# 10_Clock.net
KiCad netlist of a schematic drawn in Altium Designer
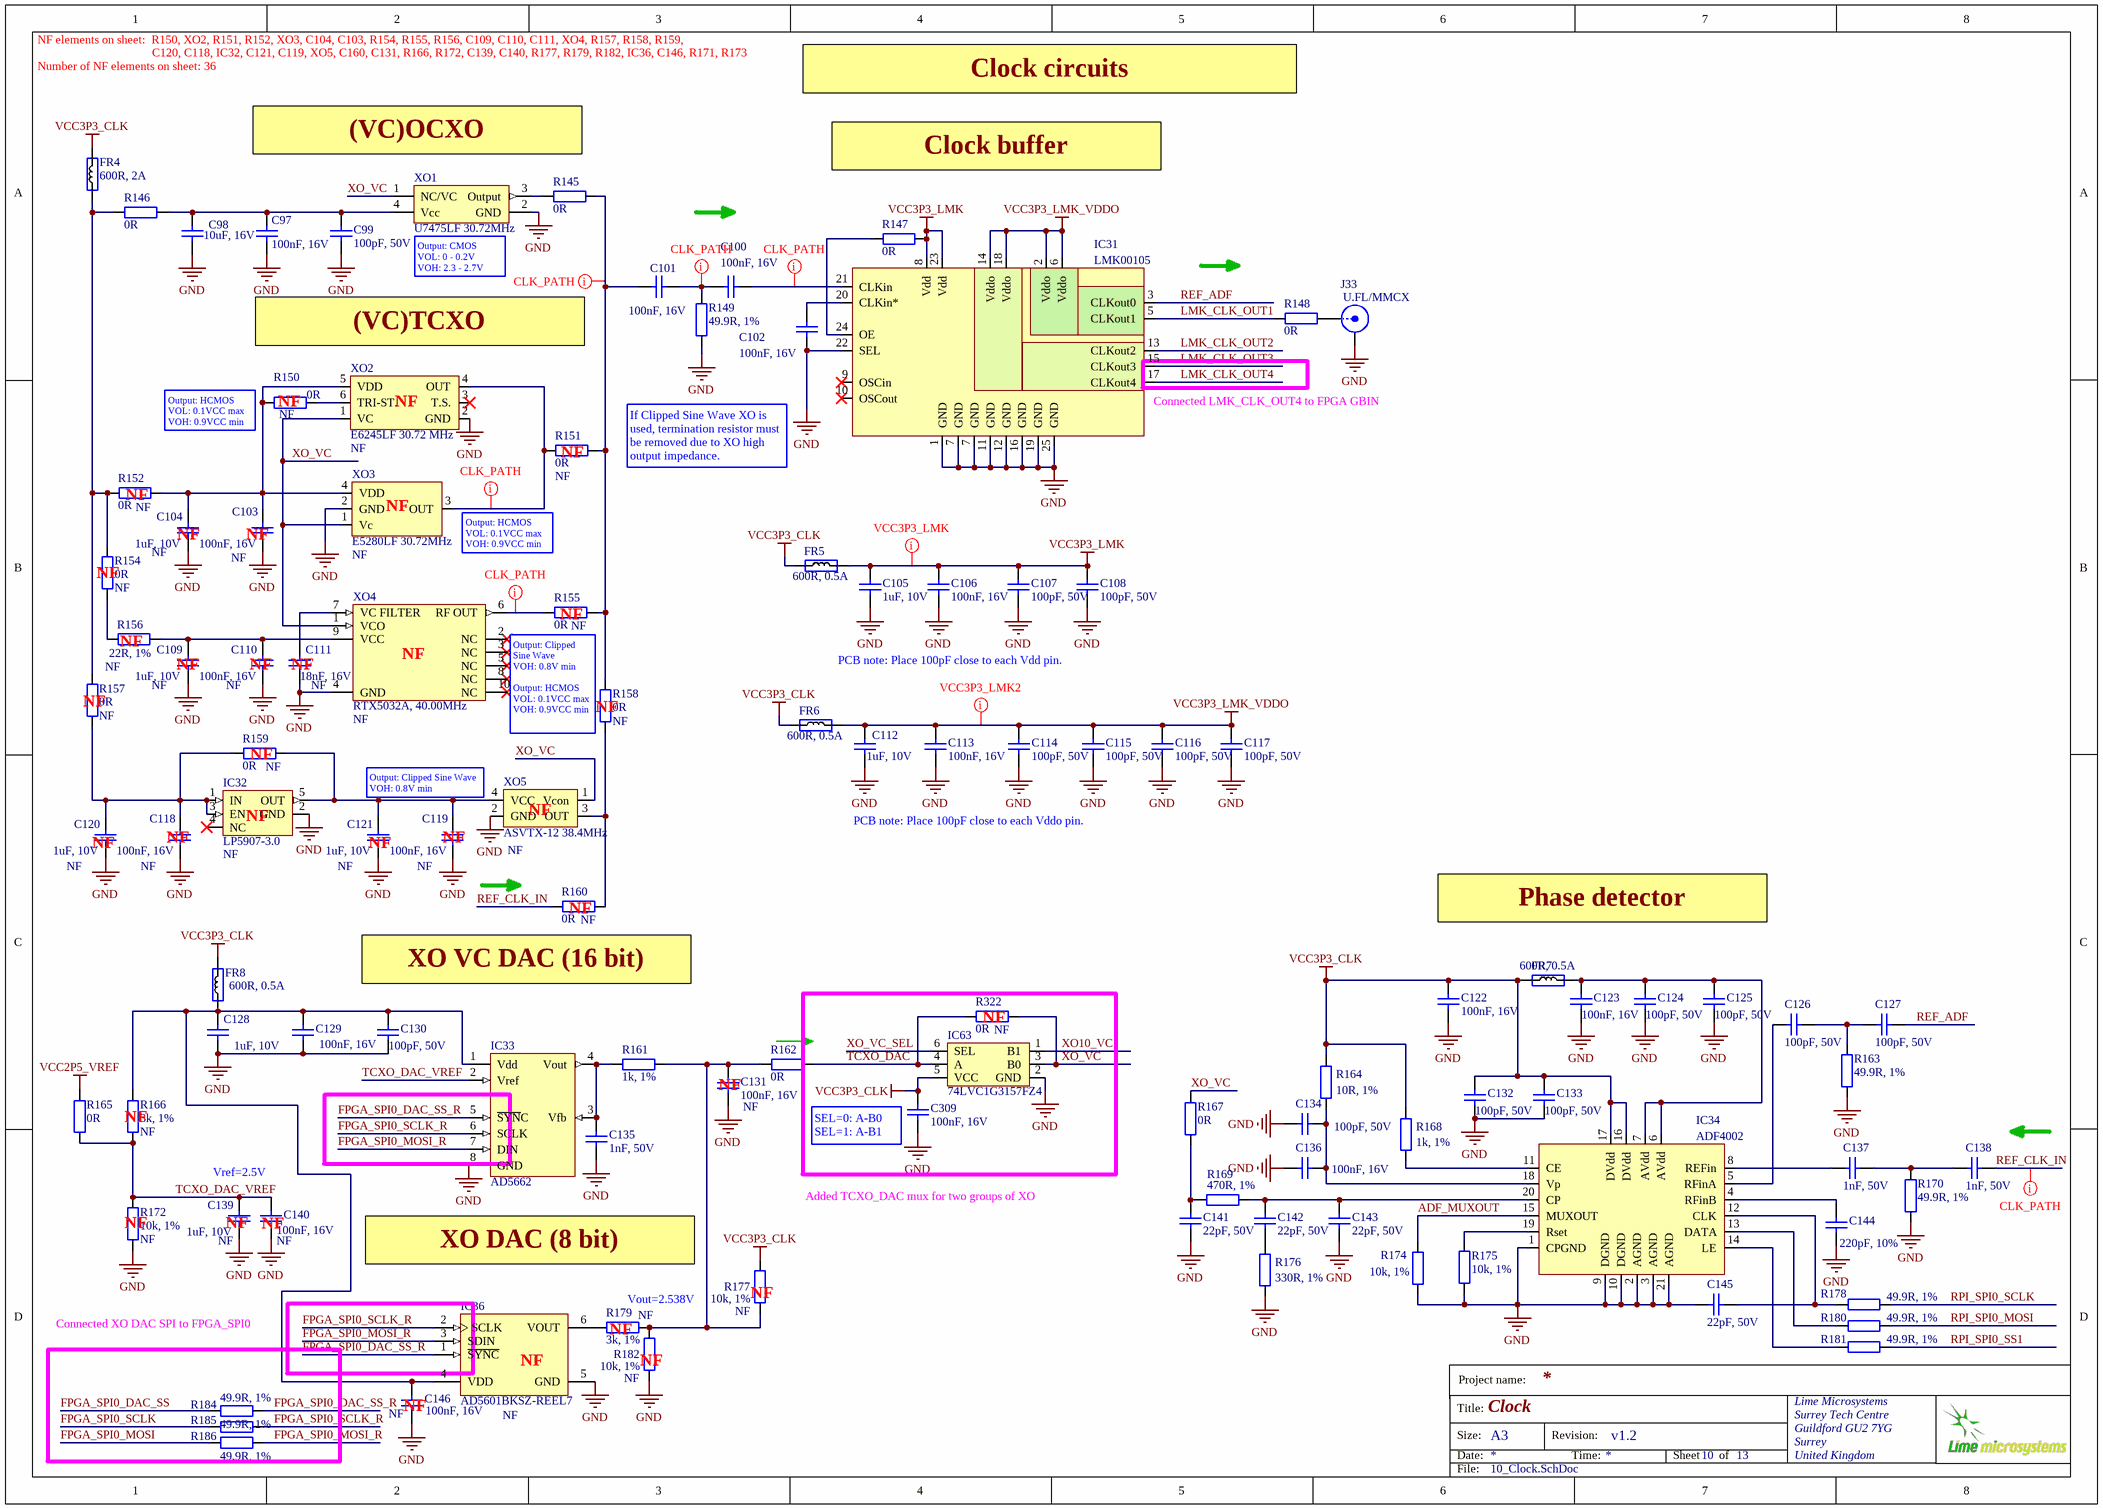
[diagram p0: 10_Clock.SchDoc]

(export (version "E")
  (design (tool "Eeschema 10.0.6"))
  (components
    (comp (ref "C97")
      (value "100nF, 16V")
      (footprint "CAP0402")
      (fields
        (field (name "MANUFACTURER") "Murata Electronics")
        (field (name "TOLERANCE") "10 %")
        (field (name "MANUFACTURER PART NUMBER") "GRM155R71C104KA88D")
      )
      (libsource (lib "LimeMicroAltiumLib_schLib") (part "Cap_0402"))
    )
    (comp (ref "C98")
      (value "10uF, 16V")
      (footprint "CAP0603")
      (fields (field (name "MANUFACTURER") "Yageo") (field (name "TOLERANCE") "±20%"))
      (libsource (lib "LimeMicroAltiumLib_schLib") (part "Cap_0603"))
    )
    (comp (ref "C99")
      (value "100pF, 50V")
      (footprint "CAP0402")
      (fields (field (name "TOLERANCE") "±5%") (field (name "MANUFACTURER") "Yageo"))
      (libsource (lib "LimeMicroAltiumLib_schLib") (part "Cap_0402"))
    )
    (comp (ref "C100")
      (value "100nF, 16V")
      (footprint "CAP0402")
      (fields
        (field (name "MANUFACTURER") "Murata Electronics")
        (field (name "TOLERANCE") "10 %")
        (field (name "MANUFACTURER PART NUMBER") "GRM155R71C104KA88D")
      )
      (libsource (lib "LimeMicroAltiumLib_schLib") (part "Cap_0402"))
    )
    (comp (ref "C101")
      (value "100nF, 16V")
      (footprint "CAP0402")
      (fields
        (field (name "MANUFACTURER") "Murata Electronics")
        (field (name "TOLERANCE") "10 %")
        (field (name "MANUFACTURER PART NUMBER") "GRM155R71C104KA88D")
      )
      (libsource (lib "LimeMicroAltiumLib_schLib") (part "Cap_0402"))
    )
    (comp (ref "C102")
      (value "100nF, 16V")
      (footprint "CAP0402")
      (fields
        (field (name "MANUFACTURER") "Murata Electronics")
        (field (name "TOLERANCE") "10 %")
        (field (name "MANUFACTURER PART NUMBER") "GRM155R71C104KA88D")
      )
      (libsource (lib "LimeMicroAltiumLib_schLib") (part "Cap_0402"))
    )
    (comp (ref "C103")
      (value "100nF, 16V")
      (footprint "CAP0402")
      (fields
        (field (name "ASSEMBLY INFO") "NF")
        (field (name "MANUFACTURER") "Murata Electronics")
        (field (name "TOLERANCE") "10 %")
        (field (name "MANUFACTURER PART NUMBER") "GRM155R71C104KA88D")
      )
      (libsource (lib "LimeMicroAltiumLib_schLib") (part "Cap_0402"))
    )
    (comp (ref "C104")
      (value "1uF, 10V")
      (footprint "CAP0402")
      (description "CAP CER 1UF 10V X5R 0402")
      (fields (field (name "ASSEMBLY INFO") "NF") (field (name "MANUFACTURER") "Yageo"))
      (libsource (lib "LimeMicroAltiumLib_schLib") (part "Cap_0402"))
    )
    (comp (ref "C105")
      (value "1uF, 10V")
      (footprint "CAP0402")
      (description "CAP CER 1UF 10V X5R 0402")
      (fields (field (name "MANUFACTURER") "Yageo") (field (name "TOLERANCE") "±20%"))
      (libsource (lib "LimeMicroAltiumLib_schLib") (part "Cap_0402"))
    )
    (comp (ref "C106")
      (value "100nF, 16V")
      (footprint "CAP0402")
      (fields
        (field (name "MANUFACTURER") "Murata Electronics")
        (field (name "TOLERANCE") "10 %")
        (field (name "MANUFACTURER PART NUMBER") "GRM155R71C104KA88D")
      )
      (libsource (lib "LimeMicroAltiumLib_schLib") (part "Cap_0402"))
    )
    (comp (ref "C107")
      (value "100pF, 50V")
      (footprint "CAP0402")
      (fields (field (name "MANUFACTURER") "Yageo") (field (name "TOLERANCE") "±5%"))
      (libsource (lib "LimeMicroAltiumLib_schLib") (part "Cap_0402"))
    )
    (comp (ref "C108")
      (value "100pF, 50V")
      (footprint "CAP0402")
      (fields (field (name "MANUFACTURER") "Yageo") (field (name "TOLERANCE") "±5%"))
      (libsource (lib "LimeMicroAltiumLib_schLib") (part "Cap_0402"))
    )
    (comp (ref "C109")
      (value "1uF, 10V")
      (footprint "CAP0402")
      (description "CAP CER 1UF 10V X5R 0402")
      (fields (field (name "ASSEMBLY INFO") "NF") (field (name "MANUFACTURER") "Yageo"))
      (libsource (lib "LimeMicroAltiumLib_schLib") (part "Cap_0402"))
    )
    (comp (ref "C110")
      (value "100nF, 16V")
      (footprint "CAP0402")
      (fields
        (field (name "ASSEMBLY INFO") "NF")
        (field (name "MANUFACTURER") "Murata Electronics")
        (field (name "TOLERANCE") "10 %")
        (field (name "MANUFACTURER PART NUMBER") "GRM155R71C104KA88D")
      )
      (libsource (lib "LimeMicroAltiumLib_schLib") (part "Cap_0402"))
    )
    (comp (ref "C111")
      (value "18nF, 16V")
      (footprint "CAP0402")
      (fields
        (field (name "ASSEMBLY INFO") "NF")
        (field (name "MANUFACTURER") "Yageo")
        (field (name "TOLERANCE") "±10%")
      )
      (libsource (lib "LimeMicroAltiumLib_schLib") (part "Cap_0402"))
    )
    (comp (ref "C112")
      (value "1uF, 10V")
      (footprint "CAP0402")
      (description "CAP CER 1UF 10V X5R 0402")
      (fields (field (name "MANUFACTURER") "Yageo") (field (name "TOLERANCE") "±20%"))
      (libsource (lib "LimeMicroAltiumLib_schLib") (part "Cap_0402"))
    )
    (comp (ref "C113")
      (value "100nF, 16V")
      (footprint "CAP0402")
      (fields
        (field (name "MANUFACTURER") "Murata Electronics")
        (field (name "TOLERANCE") "10 %")
        (field (name "MANUFACTURER PART NUMBER") "GRM155R71C104KA88D")
      )
      (libsource (lib "LimeMicroAltiumLib_schLib") (part "Cap_0402"))
    )
    (comp (ref "C114")
      (value "100pF, 50V")
      (footprint "CAP0402")
      (fields (field (name "MANUFACTURER") "Yageo") (field (name "TOLERANCE") "±5%"))
      (libsource (lib "LimeMicroAltiumLib_schLib") (part "Cap_0402"))
    )
    (comp (ref "C115")
      (value "100pF, 50V")
      (footprint "CAP0402")
      (fields (field (name "MANUFACTURER") "Yageo") (field (name "TOLERANCE") "±5%"))
      (libsource (lib "LimeMicroAltiumLib_schLib") (part "Cap_0402"))
    )
    (comp (ref "C116")
      (value "100pF, 50V")
      (footprint "CAP0402")
      (fields (field (name "MANUFACTURER") "Yageo") (field (name "TOLERANCE") "±5%"))
      (libsource (lib "LimeMicroAltiumLib_schLib") (part "Cap_0402"))
    )
    (comp (ref "C117")
      (value "100pF, 50V")
      (footprint "CAP0402")
      (fields (field (name "MANUFACTURER") "Yageo") (field (name "TOLERANCE") "±5%"))
      (libsource (lib "LimeMicroAltiumLib_schLib") (part "Cap_0402"))
    )
    (comp (ref "C118")
      (value "100nF, 16V")
      (footprint "CAP0402")
      (fields
        (field (name "ASSEMBLY INFO") "NF")
        (field (name "MANUFACTURER") "Murata Electronics")
        (field (name "TOLERANCE") "10 %")
        (field (name "MANUFACTURER PART NUMBER") "GRM155R71C104KA88D")
      )
      (libsource (lib "") (part "Cap_0402_1"))
    )
    (comp (ref "C119")
      (value "100nF, 16V")
      (footprint "CAP0402")
      (fields
        (field (name "ASSEMBLY INFO") "NF")
        (field (name "MANUFACTURER") "Murata Electronics")
        (field (name "TOLERANCE") "10 %")
        (field (name "MANUFACTURER PART NUMBER") "GRM155R71C104KA88D")
      )
      (libsource (lib "") (part "Cap_0402_1"))
    )
    (comp (ref "C120")
      (value "1uF, 10V")
      (footprint "CAP0402")
      (fields (field (name "ASSEMBLY INFO") "NF") (field (name "MANUFACTURER") "Yageo"))
      (libsource (lib "") (part "Cap_0402_1"))
    )
    (comp (ref "C121")
      (value "1uF, 10V")
      (footprint "CAP0402")
      (fields (field (name "ASSEMBLY INFO") "NF") (field (name "MANUFACTURER") "Yageo"))
      (libsource (lib "") (part "Cap_0402_1"))
    )
    (comp (ref "C122")
      (value "100nF, 16V")
      (footprint "CAP0402")
      (fields
        (field (name "MANUFACTURER") "Murata Electronics")
        (field (name "TOLERANCE") "10 %")
        (field (name "MANUFACTURER PART NUMBER") "GRM155R71C104KA88D")
      )
      (libsource (lib "LimeMicroAltiumLib_schLib") (part "Cap_0402"))
    )
    (comp (ref "C123")
      (value "100nF, 16V")
      (footprint "CAP0402")
      (fields
        (field (name "MANUFACTURER") "Murata Electronics")
        (field (name "TOLERANCE") "10 %")
        (field (name "MANUFACTURER PART NUMBER") "GRM155R71C104KA88D")
      )
      (libsource (lib "LimeMicroAltiumLib_schLib") (part "Cap_0402"))
    )
    (comp (ref "C124")
      (value "100pF, 50V")
      (footprint "CAP0402")
      (fields (field (name "MANUFACTURER") "Yageo") (field (name "TOLERANCE") "±5%"))
      (libsource (lib "LimeMicroAltiumLib_schLib") (part "Cap_0402"))
    )
    (comp (ref "C125")
      (value "100pF, 50V")
      (footprint "CAP0402")
      (fields (field (name "MANUFACTURER") "Yageo") (field (name "TOLERANCE") "±5%"))
      (libsource (lib "LimeMicroAltiumLib_schLib") (part "Cap_0402"))
    )
    (comp (ref "C126")
      (value "100pF, 50V")
      (footprint "CAP0402")
      (fields (field (name "MANUFACTURER") "Yageo") (field (name "TOLERANCE") "±5%"))
      (libsource (lib "LimeMicroAltiumLib_schLib") (part "Cap_0402"))
    )
    (comp (ref "C127")
      (value "100pF, 50V")
      (footprint "CAP0402")
      (fields (field (name "MANUFACTURER") "Yageo") (field (name "TOLERANCE") "±5%"))
      (libsource (lib "LimeMicroAltiumLib_schLib") (part "Cap_0402"))
    )
    (comp (ref "C128")
      (value "1uF, 10V")
      (footprint "CAP0402")
      (description "CAP CER 1UF 10V X5R 0402")
      (fields (field (name "MANUFACTURER") "Yageo") (field (name "TOLERANCE") "±20%"))
      (libsource (lib "LimeMicroAltiumLib_schLib") (part "Cap_0402"))
    )
    (comp (ref "C129")
      (value "100nF, 16V")
      (footprint "CAP0402")
      (fields
        (field (name "TOLERANCE") "10 %")
        (field (name "MANUFACTURER") "Murata Electronics")
        (field (name "MANUFACTURER PART NUMBER") "GRM155R71C104KA88D")
      )
      (libsource (lib "LimeFPGAboard_schLib") (part "Cap_0603"))
    )
    (comp (ref "C130")
      (value "100pF, 50V")
      (footprint "CAP0402")
      (fields (field (name "MANUFACTURER") "Yageo") (field (name "TOLERANCE") "±5%"))
      (libsource (lib "LimeMicroAltiumLib_schLib") (part "Cap_0402"))
    )
    (comp (ref "C131")
      (value "100nF, 16V")
      (footprint "CAP0402")
      (fields
        (field (name "ASSEMBLY INFO") "NF")
        (field (name "MANUFACTURER") "Murata Electronics")
        (field (name "TOLERANCE") "10 %")
        (field (name "MANUFACTURER PART NUMBER") "GRM155R71C104KA88D")
      )
      (libsource (lib "LimeMicroAltiumLib_schLib") (part "Cap_0402"))
    )
    (comp (ref "C132")
      (value "100pF, 50V")
      (footprint "CAP0402")
      (fields (field (name "MANUFACTURER") "Yageo") (field (name "TOLERANCE") "±5%"))
      (libsource (lib "LimeMicroAltiumLib_schLib") (part "Cap_0402"))
    )
    (comp (ref "C133")
      (value "100pF, 50V")
      (footprint "CAP0402")
      (fields (field (name "MANUFACTURER") "Yageo") (field (name "TOLERANCE") "±5%"))
      (libsource (lib "LimeMicroAltiumLib_schLib") (part "Cap_0402"))
    )
    (comp (ref "C134")
      (value "100pF, 50V")
      (footprint "CAP0402")
      (fields (field (name "MANUFACTURER") "Yageo") (field (name "TOLERANCE") "±5%"))
      (libsource (lib "LimeMicroAltiumLib_schLib") (part "Cap_0402"))
    )
    (comp (ref "C135")
      (value "1nF, 50V")
      (footprint "CAP0402")
      (fields
        (field (name "TOLERANCE") "±10%")
        (field (name "MANUFACTURER") "Murata Electronics North America")
      )
      (libsource (lib "LimeMicroAltiumLib_schLib") (part "Cap_0402"))
    )
    (comp (ref "C136")
      (value "100nF, 16V")
      (footprint "CAP0402")
      (fields
        (field (name "MANUFACTURER") "Murata Electronics")
        (field (name "TOLERANCE") "10 %")
        (field (name "MANUFACTURER PART NUMBER") "GRM155R71C104KA88D")
      )
      (libsource (lib "LimeMicroAltiumLib_schLib") (part "Cap_0402"))
    )
    (comp (ref "C137")
      (value "1nF, 50V")
      (footprint "CAP0402")
      (fields
        (field (name "TOLERANCE") "±10%")
        (field (name "MANUFACTURER") "Murata Electronics North America")
      )
      (libsource (lib "LimeMicroAltiumLib_schLib") (part "Cap_0402"))
    )
    (comp (ref "C138")
      (value "1nF, 50V")
      (footprint "CAP0402")
      (fields
        (field (name "TOLERANCE") "±10%")
        (field (name "MANUFACTURER") "Murata Electronics North America")
      )
      (libsource (lib "LimeMicroAltiumLib_schLib") (part "Cap_0402"))
    )
    (comp (ref "C139")
      (value "1uF, 10V")
      (footprint "CAP0402")
      (description "CAP CER 1UF 10V X5R 0402")
      (fields
        (field (name "ASSEMBLY INFO") "NF")
        (field (name "MANUFACTURER") "Yageo")
        (field (name "TOLERANCE") "±20%")
      )
      (libsource (lib "LimeMicroAltiumLib_schLib") (part "Cap_0402"))
    )
    (comp (ref "C140")
      (value "100nF, 16V")
      (footprint "CAP0402")
      (fields
        (field (name "TOLERANCE") "10 %")
        (field (name "MANUFACTURER") "Murata Electronics")
        (field (name "MANUFACTURER PART NUMBER") "GRM155R71C104KA88D")
        (field (name "ASSEMBLY INFO") "NF")
      )
      (libsource (lib "LimeFPGAboard_schLib") (part "Cap_0603"))
    )
    (comp (ref "C141")
      (value "22pF, 50V")
      (footprint "CAP0402")
      (fields (field (name "TOLERANCE") "±5%") (field (name "MANUFACTURER") "Yageo"))
      (libsource (lib "LimeMicroAltiumLib_schLib") (part "Cap_0402"))
    )
    (comp (ref "C142")
      (value "22pF, 50V")
      (footprint "CAP0402")
      (fields (field (name "TOLERANCE") "±5%") (field (name "MANUFACTURER") "Yageo"))
      (libsource (lib "LimeMicroAltiumLib_schLib") (part "Cap_0402"))
    )
    (comp (ref "C143")
      (value "22pF, 50V")
      (footprint "CAP0402")
      (fields (field (name "TOLERANCE") "±5%") (field (name "MANUFACTURER") "Yageo"))
      (libsource (lib "LimeMicroAltiumLib_schLib") (part "Cap_0402"))
    )
    (comp (ref "C144")
      (value "220pF, 10%")
      (footprint "CAP0402")
      (fields (field (name "MANUFACTURER") "Yageo") (field (name "TOLERANCE") "±10%"))
      (libsource (lib "LimeMicroAltiumLib_schLib") (part "Cap_0402"))
    )
    (comp (ref "C145")
      (value "22pF, 50V")
      (footprint "CAP0402")
      (fields (field (name "TOLERANCE") "±5%") (field (name "MANUFACTURER") "Yageo"))
      (libsource (lib "LimeMicroAltiumLib_schLib") (part "Cap_0402"))
    )
    (comp (ref "C146")
      (value "100nF, 16V")
      (footprint "CAP0402")
      (fields
        (field (name "TOLERANCE") "10 %")
        (field (name "MANUFACTURER") "Murata Electronics")
        (field (name "MANUFACTURER PART NUMBER") "GRM155R71C104KA88D")
        (field (name "ASSEMBLY INFO") "NF")
      )
      (libsource (lib "LimeFPGAboard_schLib") (part "Cap_0603"))
    )
    (comp (ref "C309")
      (value "100nF, 16V")
      (footprint "CAP0402")
      (fields
        (field (name "MANUFACTURER") "Murata Electronics")
        (field (name "TOLERANCE") "10 %")
        (field (name "MANUFACTURER PART NUMBER") "GRM155R71C104KA88D")
      )
      (libsource (lib "LimeMicroAltiumLib_schLib") (part "Cap_0402"))
    )
    (comp (ref "FR4")
      (value "600R, 2A")
      (footprint "RES0805")
      (fields (field (name "MANUFACTURER") "TDK Corporation"))
      (libsource (lib "LimeFPGAboard_schLib") (part "Ferrite"))
    )
    (comp (ref "FR5")
      (value "600R, 0.5A")
      (footprint "RES0402")
      (fields (field (name "MANUFACTURER") "Murata") (field (name "TOLERANCE") "25%"))
      (libsource (lib "LimeMicroAltiumLib_schLib") (part "Ferrite"))
    )
    (comp (ref "FR6")
      (value "600R, 0.5A")
      (footprint "RES0402")
      (fields (field (name "MANUFACTURER") "Murata") (field (name "TOLERANCE") "25%"))
      (libsource (lib "LimeMicroAltiumLib_schLib") (part "Ferrite"))
    )
    (comp (ref "FR7")
      (value "600R, 0.5A")
      (footprint "RES0402")
      (fields (field (name "MANUFACTURER") "Murata") (field (name "TOLERANCE") "25%"))
      (libsource (lib "LimeMicroAltiumLib_schLib") (part "Ferrite"))
    )
    (comp (ref "FR8")
      (value "600R, 0.5A")
      (footprint "RES0402")
      (fields (field (name "MANUFACTURER") "Murata") (field (name "TOLERANCE") "25%"))
      (libsource (lib "LimeMicroAltiumLib_schLib") (part "Ferrite"))
    )
    (comp (ref "IC31")
      (value "LMK00105")
      (footprint "LMK00105SQ")
      (fields (field (name "MANUFACTURER") "Texas Instruments"))
      (libsource (lib "LimeMicroAltiumLib_schLib") (part "LMK00105"))
    )
    (comp (ref "IC32")
      (value "LP5907-3.0")
      (footprint "SOT23-5")
      (fields (field (name "MANUFACTURER") "Texas Instruments") (field (name "ASSEMBLY INFO") "NF"))
      (libsource (lib "LimeMicroAltiumLib_schLib_r01") (part "LP5907"))
    )
    (comp (ref "IC33")
      (value "AD5662")
      (footprint "AD5662_SOT23-8")
      (fields (field (name "MANUFACTURER") "Analog Devices Inc."))
      (libsource (lib "LimeMicroAltiumLib_schLib") (part "AD5662"))
    )
    (comp (ref "IC34")
      (value "ADF4002")
      (footprint "ADF4002")
      (fields (field (name "MANUFACTURER") "Analog Devices Inc"))
      (libsource (lib "LimeMicroAltiumLib_schLib") (part "ADF4002"))
    )
    (comp (ref "IC36")
      (value "AD5601BKSZ-REEL7")
      (footprint "AD5601_SOT23-6")
      (fields
        (field (name "GENERIC PART NUMBER") "AD5601")
        (field (name "MANUFACTURER") "Analog Devices")
        (field (name "ASSEMBLY INFO") "NF")
      )
      (libsource (lib "LimeMicroAltiumLib_schLib") (part "AD5601BKSZ-REEL7"))
    )
    (comp (ref "IC63")
      (value "74LVC1G3157FZ4")
      (footprint "74LVC1G3157FZ4_SPDT_SW_DFN1410-6")
      (fields (field (name "MANUFACTURER") "Diodes"))
      (libsource (lib "LimeMicroAltiumLib_schLib_r04") (part "74LVC1G3157FZ4_SPDT_SW"))
    )
    (comp (ref "J33")
      (value "U.FL/MMCX")
      (footprint "MMCX_UFL_conn_u")
      (description "CONN UMC RCPT STR 50 OHM SMD")
      (fields (field (name "MANUFACTURER") "Molex, LLC"))
      (libsource (lib "LimeMicroAltiumLib_schLib") (part "RF_IF_connector"))
    )
    (comp (ref "R145")
      (value "0R")
      (footprint "RES0402_v2")
      (fields (field (name "MANUFACTURER") "Yageo") (field (name "TOLERANCE") "Jumper"))
      (libsource (lib "LimeMicroAltiumLib_schLib") (part "Res_0402"))
    )
    (comp (ref "R146")
      (value "0R")
      (footprint "RES0402")
      (fields (field (name "MANUFACTURER") "Yageo") (field (name "TOLERANCE") "Jumper"))
      (libsource (lib "LimeMicroAltiumLib_schLib") (part "Res_0402"))
    )
    (comp (ref "R147")
      (value "0R")
      (footprint "RES0402")
      (fields (field (name "MANUFACTURER") "Yageo") (field (name "TOLERANCE") "Jumper"))
      (libsource (lib "LimeMicroAltiumLib_schLib") (part "Res_0402"))
    )
    (comp (ref "R148")
      (value "0R")
      (footprint "RES0402")
      (fields (field (name "MANUFACTURER") "Yageo") (field (name "TOLERANCE") "Jumper"))
      (libsource (lib "") (part "Res_0402_1"))
    )
    (comp (ref "R149")
      (value "49.9R, 1%")
      (footprint "RES0402")
      (fields
        (field (name "TOLERANCE") "±1%")
        (field (name "MANUFACTURER") "Samsung Electro-Mechanics America, Inc.")
      )
      (libsource (lib "LimeMicroAltiumLib_schLib") (part "Res_0402"))
    )
    (comp (ref "R150")
      (value "0R")
      (footprint "RES0402")
      (fields
        (field (name "ASSEMBLY INFO") "NF")
        (field (name "MANUFACTURER") "Yageo")
        (field (name "TOLERANCE") "Jumper")
      )
      (libsource (lib "LimeMicroAltiumLib_schLib") (part "Res_0402"))
    )
    (comp (ref "R151")
      (value "0R")
      (footprint "RES0402_v2")
      (fields
        (field (name "ASSEMBLY INFO") "NF")
        (field (name "MANUFACTURER") "Yageo")
        (field (name "TOLERANCE") "Jumper")
      )
      (libsource (lib "LimeMicroAltiumLib_schLib") (part "Res_0402"))
    )
    (comp (ref "R152")
      (value "0R")
      (footprint "RES0402")
      (fields
        (field (name "MANUFACTURER") "Yageo")
        (field (name "TOLERANCE") "Jumper")
        (field (name "ASSEMBLY INFO") "NF")
      )
      (libsource (lib "LimeMicroAltiumLib_schLib") (part "Res_0402"))
    )
    (comp (ref "R154")
      (value "0R")
      (footprint "RES0402")
      (fields
        (field (name "ASSEMBLY INFO") "NF")
        (field (name "MANUFACTURER") "Yageo")
        (field (name "TOLERANCE") "Jumper")
      )
      (libsource (lib "LimeMicroAltiumLib_schLib") (part "Res_0402"))
    )
    (comp (ref "R155")
      (value "0R")
      (footprint "RES0402_v2")
      (fields
        (field (name "ASSEMBLY INFO") "NF")
        (field (name "MANUFACTURER") "Yageo")
        (field (name "TOLERANCE") "Jumper")
      )
      (libsource (lib "LimeMicroAltiumLib_schLib") (part "Res_0402"))
    )
    (comp (ref "R156")
      (value "22R, 1%")
      (footprint "RES0402")
      (fields
        (field (name "TOLERANCE") "±1%")
        (field (name "MANUFACTURER") "Yageo")
        (field (name "ASSEMBLY INFO") "NF")
      )
      (libsource (lib "LimeFPGAboard_schLib") (part "Res_0402"))
    )
    (comp (ref "R157")
      (value "0R")
      (footprint "RES0402")
      (fields
        (field (name "MANUFACTURER") "Yageo")
        (field (name "TOLERANCE") "Jumper")
        (field (name "ASSEMBLY INFO") "NF")
      )
      (libsource (lib "") (part "Res_0402_1"))
    )
    (comp (ref "R158")
      (value "0R")
      (footprint "RES0402_v2")
      (fields
        (field (name "ASSEMBLY INFO") "NF")
        (field (name "MANUFACTURER") "Yageo")
        (field (name "TOLERANCE") "Jumper")
      )
      (libsource (lib "") (part "Res_0402_1"))
    )
    (comp (ref "R159")
      (value "0R")
      (footprint "RES0402")
      (fields
        (field (name "MANUFACTURER") "Yageo")
        (field (name "TOLERANCE") "Jumper")
        (field (name "ASSEMBLY INFO") "NF")
      )
      (libsource (lib "") (part "Res_0402_1"))
    )
    (comp (ref "R160")
      (value "0R")
      (footprint "RES0402_v2")
      (fields
        (field (name "ASSEMBLY INFO") "NF")
        (field (name "MANUFACTURER") "Yageo")
        (field (name "TOLERANCE") "Jumper")
      )
      (libsource (lib "LimeMicroAltiumLib_schLib") (part "Res_0402"))
    )
    (comp (ref "R161")
      (value "1k, 1%")
      (footprint "RES0402")
      (fields (field (name "MANUFACTURER") "Stackpole Electronics Inc") (field (name "TOLERANCE") "±1%"))
      (libsource (lib "LimeMicroAltiumLib_schLib") (part "Res_0402"))
    )
    (comp (ref "R162")
      (value "0R")
      (footprint "RES0402")
      (fields (field (name "MANUFACTURER") "Yageo") (field (name "TOLERANCE") "Jumper"))
      (libsource (lib "LimeMicroAltiumLib_schLib") (part "Res_0402"))
    )
    (comp (ref "R163")
      (value "49.9R, 1%")
      (footprint "RES0402")
      (fields
        (field (name "TOLERANCE") "±1%")
        (field (name "MANUFACTURER") "Samsung Electro-Mechanics America, Inc.")
      )
      (libsource (lib "LimeMicroAltiumLib_schLib") (part "Res_0402"))
    )
    (comp (ref "R164")
      (value "10R, 1%")
      (footprint "RES0402")
      (fields (field (name "MANUFACTURER") "Stackpole Electronics") (field (name "TOLERANCE") "1%"))
      (libsource (lib "LimeMicroAltiumLib_schLib") (part "Res_0402"))
    )
    (comp (ref "R165")
      (value "0R")
      (footprint "RES0402_v2")
      (fields (field (name "MANUFACTURER") "Yageo") (field (name "TOLERANCE") "Jumper"))
      (libsource (lib "LimeMicroAltiumLib_schLib") (part "Res_0402"))
    )
    (comp (ref "R166")
      (value "3k, 1%")
      (footprint "RES0402")
      (fields
        (field (name "ASSEMBLY INFO") "NF")
        (field (name "TOLERANCE") "±1%")
        (field (name "MANUFACTURER") "Vishay Dale")
      )
      (libsource (lib "LimeMicroAltiumLib_schLib") (part "Res_0402"))
    )
    (comp (ref "R167")
      (value "0R")
      (footprint "RES0402")
      (fields (field (name "MANUFACTURER") "Yageo") (field (name "TOLERANCE") "Jumper"))
      (libsource (lib "LimeMicroAltiumLib_schLib") (part "Res_0402"))
    )
    (comp (ref "R168")
      (value "1k, 1%")
      (footprint "RES0402")
      (fields (field (name "MANUFACTURER") "Stackpole Electronics Inc") (field (name "TOLERANCE") "±1%"))
      (libsource (lib "LimeMicroAltiumLib_schLib") (part "Res_0402"))
    )
    (comp (ref "R169")
      (value "470R, 1%")
      (footprint "RES0402")
      (fields (field (name "TOLERANCE") "1%") (field (name "MANUFACTURER") "Yageo"))
      (libsource (lib "") (part "Res_0402_1"))
    )
    (comp (ref "R170")
      (value "49.9R, 1%")
      (footprint "RES0402")
      (fields
        (field (name "TOLERANCE") "±1%")
        (field (name "MANUFACTURER") "Samsung Electro-Mechanics America, Inc.")
      )
      (libsource (lib "LimeMicroAltiumLib_schLib") (part "Res_0402"))
    )
    (comp (ref "R172")
      (value "10k, 1%")
      (footprint "RES0402")
      (fields
        (field (name "ASSEMBLY INFO") "NF")
        (field (name "MANUFACTURER") "Yageo")
        (field (name "TOLERANCE") "±1%")
      )
      (libsource (lib "LimeMicroAltiumLib_schLib") (part "Res_0402"))
    )
    (comp (ref "R174")
      (value "10k, 1%")
      (footprint "RES0402")
      (fields (field (name "MANUFACTURER") "Yageo") (field (name "TOLERANCE") "±1%"))
      (libsource (lib "LimeMicroAltiumLib_schLib") (part "Res_0402"))
    )
    (comp (ref "R175")
      (value "10k, 1%")
      (footprint "RES0402")
      (fields (field (name "MANUFACTURER") "Yageo") (field (name "TOLERANCE") "±1%"))
      (libsource (lib "LimeMicroAltiumLib_schLib") (part "Res_0402"))
    )
    (comp (ref "R176")
      (value "330R, 1%")
      (footprint "RES0402")
      (fields (field (name "MANUFACTURER") "Yageo") (field (name "TOLERANCE") "1%"))
      (libsource (lib "LimeMicroAltiumLib_schLib") (part "Res_0402"))
    )
    (comp (ref "R177")
      (value "10k, 1%")
      (footprint "RES0402")
      (fields
        (field (name "ASSEMBLY INFO") "NF")
        (field (name "MANUFACTURER") "Yageo")
        (field (name "TOLERANCE") "±1%")
      )
      (libsource (lib "LimeMicroAltiumLib_schLib") (part "Res_0402"))
    )
    (comp (ref "R178")
      (value "49.9R, 1%")
      (footprint "RES0402")
      (fields
        (field (name "TOLERANCE") "±1%")
        (field (name "MANUFACTURER") "Samsung Electro-Mechanics America, Inc.")
      )
      (libsource (lib "LimeMicroAltiumLib_schLib") (part "Res_0402"))
    )
    (comp (ref "R179")
      (value "3k, 1%")
      (footprint "RES0402")
      (fields
        (field (name "ASSEMBLY INFO") "NF")
        (field (name "TOLERANCE") "±1%")
        (field (name "MANUFACTURER") "Vishay Dale")
      )
      (libsource (lib "LimeMicroAltiumLib_schLib") (part "Res_0402"))
    )
    (comp (ref "R180")
      (value "49.9R, 1%")
      (footprint "RES0402")
      (fields
        (field (name "TOLERANCE") "±1%")
        (field (name "MANUFACTURER") "Samsung Electro-Mechanics America, Inc.")
      )
      (libsource (lib "LimeMicroAltiumLib_schLib") (part "Res_0402"))
    )
    (comp (ref "R181")
      (value "49.9R, 1%")
      (footprint "RES0402")
      (fields
        (field (name "TOLERANCE") "±1%")
        (field (name "MANUFACTURER") "Samsung Electro-Mechanics America, Inc.")
      )
      (libsource (lib "LimeMicroAltiumLib_schLib") (part "Res_0402"))
    )
    (comp (ref "R182")
      (value "10k, 1%")
      (footprint "RES0402")
      (fields
        (field (name "ASSEMBLY INFO") "NF")
        (field (name "MANUFACTURER") "Yageo")
        (field (name "TOLERANCE") "±1%")
      )
      (libsource (lib "LimeMicroAltiumLib_schLib") (part "Res_0402"))
    )
    (comp (ref "R184")
      (value "49.9R, 1%")
      (footprint "RES0402")
      (fields
        (field (name "TOLERANCE") "±1%")
        (field (name "MANUFACTURER") "Samsung Electro-Mechanics America, Inc.")
      )
      (libsource (lib "LimeMicroAltiumLib_schLib") (part "Res_0402"))
    )
    (comp (ref "R185")
      (value "49.9R, 1%")
      (footprint "RES0402")
      (fields
        (field (name "TOLERANCE") "±1%")
        (field (name "MANUFACTURER") "Samsung Electro-Mechanics America, Inc.")
      )
      (libsource (lib "LimeMicroAltiumLib_schLib") (part "Res_0402"))
    )
    (comp (ref "R186")
      (value "49.9R, 1%")
      (footprint "RES0402")
      (fields
        (field (name "TOLERANCE") "±1%")
        (field (name "MANUFACTURER") "Samsung Electro-Mechanics America, Inc.")
      )
      (libsource (lib "LimeMicroAltiumLib_schLib") (part "Res_0402"))
    )
    (comp (ref "R322")
      (value "0R")
      (footprint "RES0402_v2")
      (fields
        (field (name "ASSEMBLY INFO") "NF")
        (field (name "MANUFACTURER") "Yageo")
        (field (name "TOLERANCE") "Jumper")
      )
      (libsource (lib "LimeMicroAltiumLib_schLib") (part "Res_0402"))
    )
    (comp (ref "XO1")
      (value "U7475LF 30.72MHz")
      (footprint "AOCJYR-10.000MHz")
      (fields (field (name "MANUFACTURER") "Rakon"))
      (libsource (lib "LimeMicroAltiumLib_schLib") (part "AOCJYR-10.000MHz"))
    )
    (comp (ref "XO2")
      (value "E6245LF 30.72 MHz")
      (footprint "RAKON_RPT7050A")
      (fields (field (name "ASSEMBLY INFO") "NF") (field (name "MANUFACTURER") "Rakon"))
      (libsource (lib "LimeMicroAltiumLib_schLib") (part "RPT7050A"))
    )
    (comp (ref "XO3")
      (value "E5280LF 30.72MHz")
      (footprint "RAKON_TXCO")
      (fields (field (name "ASSEMBLY INFO") "NF") (field (name "MANUFACTURER") "Rakon"))
      (libsource (lib "LimeMicroAltiumLib_schLib") (part "TXCO"))
    )
    (comp (ref "XO4")
      (value "RTX5032A, 40.00MHz")
      (footprint "RAKON_RTX5032A")
      (fields (field (name "ASSEMBLY INFO") "NF") (field (name "MANUFACTURER") "Rakon"))
      (libsource (lib "LimeMicroAltiumLib_schLib") (part "Rakon_RTX5032A"))
    )
    (comp (ref "XO5")
      (value "ASVTX-12 38.4MHz")
      (footprint "CRYSTAL_4-LCC_2P5x2P0")
      (description "Oscillator Crystal")
      (fields (field (name "MANUFACTURER") "Abracon") (field (name "ASSEMBLY INFO") "NF"))
      (libsource (lib "LimeMicroAltiumLib_schLib_r01") (part "ASVTX-12-A-38.400MHZ-H10-T_CRYSTAL"))
    )
  )
  (nets
    (net (code "2") (name "/ADF_MUXOUT") (class "Default")
      (node (ref "IC34") (pin "15") (pinfunction "MUXOUT_15") (pintype "passive"))
      (node (ref "R174") (pin "1") (pinfunction "1_1") (pintype "passive"))
    )
    (net (code "3") (name "/FPGA_SPI0_DAC_SS") (class "Default")
      (node (ref "R184") (pin "2") (pinfunction "2_2") (pintype "passive"))
    )
    (net (code "4") (name "/FPGA_SPI0_DAC_SS_R") (class "Default")
      (node (ref "IC33") (pin "5") (pinfunction "~{SYN}C_5") (pintype "input"))
      (node (ref "IC36") (pin "1") (pinfunction "~{SYNC}_1") (pintype "input"))
      (node (ref "R184") (pin "1") (pinfunction "1_1") (pintype "passive"))
    )
    (net (code "5") (name "/FPGA_SPI0_MOSI") (class "Default")
      (node (ref "R186") (pin "2") (pinfunction "2_2") (pintype "passive"))
    )
    (net (code "6") (name "/FPGA_SPI0_MOSI_R") (class "Default")
      (node (ref "IC33") (pin "7") (pinfunction "DIN_7") (pintype "input"))
      (node (ref "IC36") (pin "3") (pinfunction "SDIN_3") (pintype "input"))
      (node (ref "R186") (pin "1") (pinfunction "1_1") (pintype "passive"))
    )
    (net (code "7") (name "/FPGA_SPI0_SCLK") (class "Default")
      (node (ref "R185") (pin "2") (pinfunction "2_2") (pintype "passive"))
    )
    (net (code "8") (name "/FPGA_SPI0_SCLK_R") (class "Default")
      (node (ref "IC33") (pin "6") (pinfunction "SCLK_6") (pintype "input"))
      (node (ref "IC36") (pin "2") (pinfunction "SCLK_2") (pintype "input"))
      (node (ref "R185") (pin "1") (pinfunction "1_1") (pintype "passive"))
    )
    (net (code "9") (name "/LMK_CLK_OUT1") (class "Default")
      (node (ref "IC31") (pin "5") (pinfunction "CLKout1_5") (pintype "passive"))
      (node (ref "R148") (pin "2") (pinfunction "2_2") (pintype "passive"))
    )
    (net (code "10") (name "/LMK_CLK_OUT2") (class "Default")
      (node (ref "IC31") (pin "13") (pinfunction "CLKout2_13") (pintype "passive"))
    )
    (net (code "11") (name "/LMK_CLK_OUT3") (class "Default")
      (node (ref "IC31") (pin "15") (pinfunction "CLKout3_15") (pintype "passive"))
    )
    (net (code "12") (name "/LMK_CLK_OUT4") (class "Default")
      (node (ref "IC31") (pin "17") (pinfunction "CLKout4_17") (pintype "passive"))
    )
    (net (code "13") (name "/REF_ADF") (class "Default")
      (node (ref "C127") (pin "2") (pinfunction "2_2") (pintype "passive"))
      (node (ref "IC31") (pin "3") (pinfunction "CLKout0_3") (pintype "passive"))
    )
    (net (code "14") (name "/REF_CLK_IN") (class "Default")
      (node (ref "C138") (pin "2") (pinfunction "2_2") (pintype "passive"))
      (node (ref "R160") (pin "2") (pinfunction "2_2") (pintype "passive"))
    )
    (net (code "15") (name "/RPI_SPI0_MOSI") (class "Default")
      (node (ref "R180") (pin "1") (pinfunction "1_1") (pintype "passive"))
    )
    (net (code "16") (name "/RPI_SPI0_SCLK") (class "Default")
      (node (ref "R178") (pin "1") (pinfunction "1_1") (pintype "passive"))
    )
    (net (code "17") (name "/RPI_SPI0_SS1") (class "Default")
      (node (ref "R181") (pin "1") (pinfunction "1_1") (pintype "passive"))
    )
    (net (code "18") (name "/TCXO_DAC") (class "Default")
      (node (ref "IC63") (pin "4") (pinfunction "A_4") (pintype "passive"))
      (node (ref "R162") (pin "1") (pinfunction "1_1") (pintype "passive"))
      (node (ref "R322") (pin "2") (pinfunction "2_2") (pintype "passive"))
    )
    (net (code "19") (name "/TCXO_DAC_VREF") (class "Default")
      (node (ref "C139") (pin "2") (pinfunction "2_2") (pintype "passive"))
      (node (ref "C140") (pin "1") (pinfunction "1_1") (pintype "passive"))
      (node (ref "IC33") (pin "2") (pinfunction "Vref_2") (pintype "input"))
      (node (ref "R165") (pin "1") (pinfunction "1_1") (pintype "passive"))
      (node (ref "R166") (pin "1") (pinfunction "1_1") (pintype "passive"))
      (node (ref "R172") (pin "1") (pinfunction "1_1") (pintype "passive"))
    )
    (net (code "20") (name "/XO10_VC") (class "Default")
      (node (ref "IC63") (pin "1") (pinfunction "B1_1") (pintype "passive"))
    )
    (net (code "21") (name "/XO_VC") (class "Default")
      (node (ref "IC63") (pin "3") (pinfunction "B0_3") (pintype "passive"))
      (node (ref "R167") (pin "2") (pinfunction "2_2") (pintype "passive"))
      (node (ref "R322") (pin "1") (pinfunction "1_1") (pintype "passive"))
      (node (ref "XO1") (pin "1") (pinfunction "NC/VC_1") (pintype "passive"))
      (node (ref "XO2") (pin "1") (pinfunction "VC_1") (pintype "passive"))
      (node (ref "XO3") (pin "1") (pinfunction "Vc_1") (pintype "passive"))
      (node (ref "XO4") (pin "1") (pinfunction "VCO_1") (pintype "input"))
      (node (ref "XO5") (pin "1") (pinfunction "Vcon_1") (pintype "passive"))
    )
    (net (code "22") (name "/XO_VC_SEL") (class "Default")
      (node (ref "IC63") (pin "6") (pinfunction "SEL_6") (pintype "passive"))
    )
    (net (code "23") (name "GND") (class "Default")
      (node (ref "C102") (pin "1") (pinfunction "1_1") (pintype "passive"))
      (node (ref "C103") (pin "1") (pinfunction "1_1") (pintype "passive"))
      (node (ref "C104") (pin "1") (pinfunction "1_1") (pintype "passive"))
      (node (ref "C105") (pin "1") (pinfunction "1_1") (pintype "passive"))
      (node (ref "C106") (pin "1") (pinfunction "1_1") (pintype "passive"))
      (node (ref "C107") (pin "1") (pinfunction "1_1") (pintype "passive"))
      (node (ref "C108") (pin "1") (pinfunction "1_1") (pintype "passive"))
      (node (ref "C109") (pin "1") (pinfunction "1_1") (pintype "passive"))
      (node (ref "C110") (pin "1") (pinfunction "1_1") (pintype "passive"))
      (node (ref "C111") (pin "1") (pinfunction "1_1") (pintype "passive"))
      (node (ref "C112") (pin "1") (pinfunction "1_1") (pintype "passive"))
      (node (ref "C113") (pin "1") (pinfunction "1_1") (pintype "passive"))
      (node (ref "C114") (pin "1") (pinfunction "1_1") (pintype "passive"))
      (node (ref "C115") (pin "1") (pinfunction "1_1") (pintype "passive"))
      (node (ref "C116") (pin "1") (pinfunction "1_1") (pintype "passive"))
      (node (ref "C117") (pin "1") (pinfunction "1_1") (pintype "passive"))
      (node (ref "C118") (pin "1") (pinfunction "1_1") (pintype "passive"))
      (node (ref "C119") (pin "1") (pinfunction "1_1") (pintype "passive"))
      (node (ref "C120") (pin "1") (pinfunction "1_1") (pintype "passive"))
      (node (ref "C121") (pin "1") (pinfunction "1_1") (pintype "passive"))
      (node (ref "C122") (pin "1") (pinfunction "1_1") (pintype "passive"))
      (node (ref "C123") (pin "1") (pinfunction "1_1") (pintype "passive"))
      (node (ref "C124") (pin "2") (pinfunction "2_2") (pintype "passive"))
      (node (ref "C125") (pin "2") (pinfunction "2_2") (pintype "passive"))
      (node (ref "C128") (pin "1") (pinfunction "1_1") (pintype "passive"))
      (node (ref "C129") (pin "2") (pinfunction "2_2") (pintype "passive"))
      (node (ref "C130") (pin "2") (pinfunction "2_2") (pintype "passive"))
      (node (ref "C131") (pin "1") (pinfunction "1_1") (pintype "passive"))
      (node (ref "C132") (pin "2") (pinfunction "2_2") (pintype "passive"))
      (node (ref "C133") (pin "2") (pinfunction "2_2") (pintype "passive"))
      (node (ref "C134") (pin "1") (pinfunction "1_1") (pintype "passive"))
      (node (ref "C135") (pin "2") (pinfunction "2_2") (pintype "passive"))
      (node (ref "C136") (pin "2") (pinfunction "2_2") (pintype "passive"))
      (node (ref "C139") (pin "1") (pinfunction "1_1") (pintype "passive"))
      (node (ref "C140") (pin "2") (pinfunction "2_2") (pintype "passive"))
      (node (ref "C141") (pin "1") (pinfunction "1_1") (pintype "passive"))
      (node (ref "C143") (pin "1") (pinfunction "1_1") (pintype "passive"))
      (node (ref "C144") (pin "2") (pinfunction "2_2") (pintype "passive"))
      (node (ref "C145") (pin "2") (pinfunction "2_2") (pintype "passive"))
      (node (ref "C146") (pin "2") (pinfunction "2_2") (pintype "passive"))
      (node (ref "C309") (pin "1") (pinfunction "1_1") (pintype "passive"))
      (node (ref "C97") (pin "1") (pinfunction "1_1") (pintype "passive"))
      (node (ref "C98") (pin "1") (pinfunction "1_1") (pintype "passive"))
      (node (ref "C99") (pin "2") (pinfunction "2_2") (pintype "passive"))
      (node (ref "IC31") (pin "1") (pinfunction "GND_1") (pintype "passive"))
      (node (ref "IC31") (pin "11") (pinfunction "GND_11") (pintype "passive"))
      (node (ref "IC31") (pin "12") (pinfunction "GND_12") (pintype "passive"))
      (node (ref "IC31") (pin "16") (pinfunction "GND_16") (pintype "passive"))
      (node (ref "IC31") (pin "19") (pinfunction "GND_19") (pintype "passive"))
      (node (ref "IC31") (pin "22") (pinfunction "SEL_22") (pintype "passive"))
      (node (ref "IC31") (pin "25") (pinfunction "GND_25") (pintype "passive"))
      (node (ref "IC31") (pin "7") (pinfunction "GND_7") (pintype "passive"))
      (node (ref "IC32") (pin "2") (pinfunction "GND_2") (pintype "passive"))
      (node (ref "IC33") (pin "8") (pinfunction "GND_8") (pintype "passive"))
      (node (ref "IC34") (pin "1") (pinfunction "CPGND_1") (pintype "passive"))
      (node (ref "IC34") (pin "10") (pinfunction "DGND_10") (pintype "passive"))
      (node (ref "IC34") (pin "2") (pinfunction "AGND_2") (pintype "passive"))
      (node (ref "IC34") (pin "21") (pinfunction "AGND_21") (pintype "passive"))
      (node (ref "IC34") (pin "3") (pinfunction "AGND_3") (pintype "passive"))
      (node (ref "IC34") (pin "9") (pinfunction "DGND_9") (pintype "passive"))
      (node (ref "IC36") (pin "5") (pinfunction "GND_5") (pintype "power_in"))
      (node (ref "IC63") (pin "2") (pinfunction "GND_2") (pintype "passive"))
      (node (ref "J33") (pin "2") (pinfunction "Y_2") (pintype "passive"))
      (node (ref "R149") (pin "1") (pinfunction "1_1") (pintype "passive"))
      (node (ref "R163") (pin "1") (pinfunction "1_1") (pintype "passive"))
      (node (ref "R170") (pin "1") (pinfunction "1_1") (pintype "passive"))
      (node (ref "R172") (pin "2") (pinfunction "2_2") (pintype "passive"))
      (node (ref "R174") (pin "2") (pinfunction "2_2") (pintype "passive"))
      (node (ref "R175") (pin "2") (pinfunction "2_2") (pintype "passive"))
      (node (ref "R176") (pin "1") (pinfunction "1_1") (pintype "passive"))
      (node (ref "R182") (pin "2") (pinfunction "2_2") (pintype "passive"))
      (node (ref "XO1") (pin "2") (pinfunction "GND_2") (pintype "passive"))
      (node (ref "XO2") (pin "2") (pinfunction "GND_2") (pintype "passive"))
      (node (ref "XO3") (pin "2") (pinfunction "GND_2") (pintype "passive"))
      (node (ref "XO4") (pin "4") (pinfunction "GND_4") (pintype "passive"))
      (node (ref "XO5") (pin "2") (pinfunction "GND_2") (pintype "passive"))
    )
    (net (code "24") (name "Net-(C100-Pad2)") (class "Default")
      (node (ref "C100") (pin "2") (pinfunction "2_2") (pintype "passive"))
      (node (ref "C101") (pin "1") (pinfunction "1_1") (pintype "passive"))
      (node (ref "R149") (pin "2") (pinfunction "2_2") (pintype "passive"))
    )
    (net (code "25") (name "Net-(C101-Pad2)") (class "Default")
      (node (ref "C101") (pin "2") (pinfunction "2_2") (pintype "passive"))
      (node (ref "R145") (pin "1") (pinfunction "1_1") (pintype "passive"))
      (node (ref "R151") (pin "1") (pinfunction "1_1") (pintype "passive"))
      (node (ref "R155") (pin "2") (pinfunction "2_2") (pintype "passive"))
      (node (ref "R158") (pin "1") (pinfunction "1_1") (pintype "passive"))
    )
    (net (code "26") (name "Net-(C123-Pad2)") (class "Default")
      (node (ref "C123") (pin "2") (pinfunction "2_2") (pintype "passive"))
      (node (ref "C124") (pin "1") (pinfunction "1_1") (pintype "passive"))
      (node (ref "C125") (pin "1") (pinfunction "1_1") (pintype "passive"))
      (node (ref "FR7") (pin "2") (pinfunction "2_2") (pintype "passive"))
      (node (ref "IC34") (pin "6") (pinfunction "AVdd_6") (pintype "passive"))
      (node (ref "IC34") (pin "7") (pinfunction "AVdd_7") (pintype "passive"))
    )
    (net (code "27") (name "Net-(C126-Pad2)") (class "Default")
      (node (ref "C126") (pin "2") (pinfunction "2_2") (pintype "passive"))
      (node (ref "C127") (pin "1") (pinfunction "1_1") (pintype "passive"))
      (node (ref "R163") (pin "2") (pinfunction "2_2") (pintype "passive"))
    )
    (net (code "28") (name "Net-(C131-Pad2)") (class "Default")
      (node (ref "C131") (pin "2") (pinfunction "2_2") (pintype "passive"))
      (node (ref "R161") (pin "1") (pinfunction "1_1") (pintype "passive"))
      (node (ref "R162") (pin "2") (pinfunction "2_2") (pintype "passive"))
      (node (ref "R177") (pin "2") (pinfunction "2_2") (pintype "passive"))
      (node (ref "R179") (pin "1") (pinfunction "1_1") (pintype "passive"))
      (node (ref "R182") (pin "1") (pinfunction "1_1") (pintype "passive"))
    )
    (net (code "29") (name "Net-(C137-Pad2)") (class "Default")
      (node (ref "C137") (pin "2") (pinfunction "2_2") (pintype "passive"))
      (node (ref "C138") (pin "1") (pinfunction "1_1") (pintype "passive"))
      (node (ref "R170") (pin "2") (pinfunction "2_2") (pintype "passive"))
    )
    (net (code "30") (name "Net-(C141-Pad2)") (class "Default")
      (node (ref "C141") (pin "2") (pinfunction "2_2") (pintype "passive"))
      (node (ref "R167") (pin "1") (pinfunction "1_1") (pintype "passive"))
      (node (ref "R169") (pin "2") (pinfunction "2_2") (pintype "passive"))
    )
    (net (code "31") (name "Net-(C142-Pad1)") (class "Default")
      (node (ref "C142") (pin "1") (pinfunction "1_1") (pintype "passive"))
      (node (ref "R176") (pin "2") (pinfunction "2_2") (pintype "passive"))
    )
    (net (code "32") (name "Net-(FR4-Pad2)") (class "Default")
      (node (ref "FR4") (pin "2") (pinfunction "2_2") (pintype "passive"))
      (node (ref "R146") (pin "1") (pinfunction "1_1") (pintype "passive"))
      (node (ref "R152") (pin "2") (pinfunction "2_2") (pintype "passive"))
      (node (ref "R154") (pin "1") (pinfunction "1_1") (pintype "passive"))
      (node (ref "R157") (pin "1") (pinfunction "1_1") (pintype "passive"))
    )
    (net (code "33") (name "Net-(IC31-CLKin)") (class "Default")
      (node (ref "C100") (pin "1") (pinfunction "1_1") (pintype "passive"))
      (node (ref "IC31") (pin "21") (pinfunction "CLKin_21") (pintype "passive"))
    )
    (net (code "34") (name "Net-(IC31-CLKin*)") (class "Default")
      (node (ref "C102") (pin "2") (pinfunction "2_2") (pintype "passive"))
      (node (ref "IC31") (pin "20") (pinfunction "CLKin*_20") (pintype "passive"))
    )
    (net (code "35") (name "Net-(IC31-OE)") (class "Default")
      (node (ref "IC31") (pin "24") (pinfunction "OE_24") (pintype "passive"))
      (node (ref "R147") (pin "1") (pinfunction "1_1") (pintype "passive"))
    )
    (net (code "36") (name "Net-(IC32-EN)") (class "Default")
      (node (ref "C118") (pin "2") (pinfunction "2_2") (pintype "passive"))
      (node (ref "C120") (pin "2") (pinfunction "2_2") (pintype "passive"))
      (node (ref "IC32") (pin "1") (pinfunction "IN_1") (pintype "input"))
      (node (ref "IC32") (pin "3") (pinfunction "EN_3") (pintype "input"))
      (node (ref "R157") (pin "2") (pinfunction "2_2") (pintype "passive"))
      (node (ref "R159") (pin "2") (pinfunction "2_2") (pintype "passive"))
    )
    (net (code "37") (name "Net-(IC32-OUT)") (class "Default")
      (node (ref "C119") (pin "2") (pinfunction "2_2") (pintype "passive"))
      (node (ref "C121") (pin "2") (pinfunction "2_2") (pintype "passive"))
      (node (ref "IC32") (pin "5") (pinfunction "OUT_5") (pintype "output"))
      (node (ref "R159") (pin "1") (pinfunction "1_1") (pintype "passive"))
      (node (ref "XO5") (pin "4") (pinfunction "VCC_4") (pintype "passive"))
    )
    (net (code "38") (name "Net-(IC33-Vdd)") (class "Default")
      (node (ref "C128") (pin "2") (pinfunction "2_2") (pintype "passive"))
      (node (ref "C129") (pin "1") (pinfunction "1_1") (pintype "passive"))
      (node (ref "C130") (pin "1") (pinfunction "1_1") (pintype "passive"))
      (node (ref "C146") (pin "1") (pinfunction "1_1") (pintype "passive"))
      (node (ref "FR8") (pin "1") (pinfunction "1_1") (pintype "passive"))
      (node (ref "IC33") (pin "1") (pinfunction "Vdd_1") (pintype "power_in"))
      (node (ref "IC36") (pin "4") (pinfunction "VDD_4") (pintype "power_in"))
      (node (ref "R166") (pin "2") (pinfunction "2_2") (pintype "passive"))
    )
    (net (code "39") (name "Net-(IC33-Vfb)") (class "Default")
      (node (ref "C135") (pin "1") (pinfunction "1_1") (pintype "passive"))
      (node (ref "IC33") (pin "3") (pinfunction "Vfb_3") (pintype "input"))
      (node (ref "IC33") (pin "4") (pinfunction "Vout_4") (pintype "output"))
      (node (ref "R161") (pin "2") (pinfunction "2_2") (pintype "passive"))
    )
    (net (code "40") (name "Net-(IC34-CE)") (class "Default")
      (node (ref "IC34") (pin "11") (pinfunction "CE_11") (pintype "passive"))
      (node (ref "R168") (pin "1") (pinfunction "1_1") (pintype "passive"))
    )
    (net (code "41") (name "Net-(IC34-CLK)") (class "Default")
      (node (ref "C145") (pin "1") (pinfunction "1_1") (pintype "passive"))
      (node (ref "IC34") (pin "12") (pinfunction "CLK_12") (pintype "passive"))
      (node (ref "R178") (pin "2") (pinfunction "2_2") (pintype "passive"))
    )
    (net (code "42") (name "Net-(IC34-CP)") (class "Default")
      (node (ref "C142") (pin "2") (pinfunction "2_2") (pintype "passive"))
      (node (ref "C143") (pin "2") (pinfunction "2_2") (pintype "passive"))
      (node (ref "IC34") (pin "20") (pinfunction "CP_20") (pintype "passive"))
      (node (ref "R169") (pin "1") (pinfunction "1_1") (pintype "passive"))
    )
    (net (code "43") (name "Net-(IC34-DATA)") (class "Default")
      (node (ref "IC34") (pin "13") (pinfunction "DATA_13") (pintype "passive"))
      (node (ref "R180") (pin "2") (pinfunction "2_2") (pintype "passive"))
    )
    (net (code "44") (name "Net-(IC34-LE)") (class "Default")
      (node (ref "IC34") (pin "14") (pinfunction "LE_14") (pintype "passive"))
      (node (ref "R181") (pin "2") (pinfunction "2_2") (pintype "passive"))
    )
    (net (code "45") (name "Net-(IC34-REFin)") (class "Default")
      (node (ref "C137") (pin "1") (pinfunction "1_1") (pintype "passive"))
      (node (ref "IC34") (pin "8") (pinfunction "REFin_8") (pintype "passive"))
    )
    (net (code "46") (name "Net-(IC34-RFinA)") (class "Default")
      (node (ref "C126") (pin "1") (pinfunction "1_1") (pintype "passive"))
      (node (ref "IC34") (pin "5") (pinfunction "RFinA_5") (pintype "passive"))
    )
    (net (code "47") (name "Net-(IC34-RFinB)") (class "Default")
      (node (ref "C144") (pin "1") (pinfunction "1_1") (pintype "passive"))
      (node (ref "IC34") (pin "4") (pinfunction "RFinB_4") (pintype "passive"))
    )
    (net (code "48") (name "Net-(IC34-Rset)") (class "Default")
      (node (ref "IC34") (pin "19") (pinfunction "Rset_19") (pintype "passive"))
      (node (ref "R175") (pin "1") (pinfunction "1_1") (pintype "passive"))
    )
    (net (code "49") (name "Net-(IC34-Vp)") (class "Default")
      (node (ref "C134") (pin "2") (pinfunction "2_2") (pintype "passive"))
      (node (ref "C136") (pin "1") (pinfunction "1_1") (pintype "passive"))
      (node (ref "IC34") (pin "18") (pinfunction "Vp_18") (pintype "passive"))
      (node (ref "R164") (pin "1") (pinfunction "1_1") (pintype "passive"))
    )
    (net (code "50") (name "Net-(IC36-VOUT)") (class "Default")
      (node (ref "IC36") (pin "6") (pinfunction "VOUT_6") (pintype "tri_state"))
      (node (ref "R179") (pin "2") (pinfunction "2_2") (pintype "passive"))
    )
    (net (code "51") (name "Net-(J33-X)") (class "Default")
      (node (ref "J33") (pin "1") (pinfunction "X_1") (pintype "passive"))
      (node (ref "R148") (pin "1") (pinfunction "1_1") (pintype "passive"))
    )
    (net (code "52") (name "Net-(R154-Pad2)") (class "Default")
      (node (ref "R154") (pin "2") (pinfunction "2_2") (pintype "passive"))
      (node (ref "R156") (pin "1") (pinfunction "1_1") (pintype "passive"))
    )
    (net (code "53") (name "Net-(XO1-Output)") (class "Default")
      (node (ref "R145") (pin "2") (pinfunction "2_2") (pintype "passive"))
      (node (ref "XO1") (pin "3") (pinfunction "Output_3") (pintype "output"))
    )
    (net (code "54") (name "Net-(XO1-Vcc)") (class "Default")
      (node (ref "C97") (pin "2") (pinfunction "2_2") (pintype "passive"))
      (node (ref "C98") (pin "2") (pinfunction "2_2") (pintype "passive"))
      (node (ref "C99") (pin "1") (pinfunction "1_1") (pintype "passive"))
      (node (ref "R146") (pin "2") (pinfunction "2_2") (pintype "passive"))
      (node (ref "XO1") (pin "4") (pinfunction "Vcc_4") (pintype "power_in"))
    )
    (net (code "55") (name "Net-(XO2-OUT)") (class "Default")
      (node (ref "R151") (pin "2") (pinfunction "2_2") (pintype "passive"))
      (node (ref "XO2") (pin "4") (pinfunction "OUT_4") (pintype "passive"))
      (node (ref "XO3") (pin "3") (pinfunction "OUT_3") (pintype "passive"))
    )
    (net (code "56") (name "Net-(XO2-TRI-ST.)") (class "Default")
      (node (ref "R150") (pin "1") (pinfunction "1_1") (pintype "passive"))
      (node (ref "XO2") (pin "6") (pinfunction "TRI-ST._6") (pintype "passive"))
    )
    (net (code "57") (name "Net-(XO2-VDD)") (class "Default")
      (node (ref "C103") (pin "2") (pinfunction "2_2") (pintype "passive"))
      (node (ref "C104") (pin "2") (pinfunction "2_2") (pintype "passive"))
      (node (ref "R150") (pin "2") (pinfunction "2_2") (pintype "passive"))
      (node (ref "R152") (pin "1") (pinfunction "1_1") (pintype "passive"))
      (node (ref "XO2") (pin "5") (pinfunction "VDD_5") (pintype "passive"))
      (node (ref "XO3") (pin "4") (pinfunction "VDD_4") (pintype "passive"))
    )
    (net (code "58") (name "Net-(XO4-RF_OUT)") (class "Default")
      (node (ref "R155") (pin "1") (pinfunction "1_1") (pintype "passive"))
      (node (ref "XO4") (pin "6") (pinfunction "RF_OUT_6") (pintype "output"))
    )
    (net (code "59") (name "Net-(XO4-VCC)") (class "Default")
      (node (ref "C109") (pin "2") (pinfunction "2_2") (pintype "passive"))
      (node (ref "C110") (pin "2") (pinfunction "2_2") (pintype "passive"))
      (node (ref "R156") (pin "2") (pinfunction "2_2") (pintype "passive"))
      (node (ref "XO4") (pin "9") (pinfunction "VCC_9") (pintype "power_in"))
    )
    (net (code "60") (name "Net-(XO4-VC_FILTER)") (class "Default")
      (node (ref "C111") (pin "2") (pinfunction "2_2") (pintype "passive"))
      (node (ref "XO4") (pin "7") (pinfunction "VC_FILTER_7") (pintype "input"))
    )
    (net (code "61") (name "Net-(XO5-OUT)") (class "Default")
      (node (ref "R158") (pin "2") (pinfunction "2_2") (pintype "passive"))
      (node (ref "R160") (pin "1") (pinfunction "1_1") (pintype "passive"))
      (node (ref "XO5") (pin "3") (pinfunction "OUT_3") (pintype "passive"))
    )
    (net (code "62") (name "VCC2P5_VREF") (class "Default")
      (node (ref "R165") (pin "2") (pinfunction "2_2") (pintype "passive"))
    )
    (net (code "63") (name "VCC3P3_CLK") (class "Default")
      (node (ref "C122") (pin "2") (pinfunction "2_2") (pintype "passive"))
      (node (ref "C132") (pin "1") (pinfunction "1_1") (pintype "passive"))
      (node (ref "C133") (pin "1") (pinfunction "1_1") (pintype "passive"))
      (node (ref "C309") (pin "2") (pinfunction "2_2") (pintype "passive"))
      (node (ref "FR4") (pin "1") (pinfunction "1_1") (pintype "passive"))
      (node (ref "FR5") (pin "1") (pinfunction "1_1") (pintype "passive"))
      (node (ref "FR6") (pin "1") (pinfunction "1_1") (pintype "passive"))
      (node (ref "FR7") (pin "1") (pinfunction "1_1") (pintype "passive"))
      (node (ref "FR8") (pin "2") (pinfunction "2_2") (pintype "passive"))
      (node (ref "IC34") (pin "16") (pinfunction "DVdd_16") (pintype "passive"))
      (node (ref "IC34") (pin "17") (pinfunction "DVdd_17") (pintype "passive"))
      (node (ref "IC63") (pin "5") (pinfunction "VCC_5") (pintype "passive"))
      (node (ref "R164") (pin "2") (pinfunction "2_2") (pintype "passive"))
      (node (ref "R168") (pin "2") (pinfunction "2_2") (pintype "passive"))
      (node (ref "R177") (pin "1") (pinfunction "1_1") (pintype "passive"))
    )
    (net (code "64") (name "VCC3P3_LMK") (class "Default")
      (node (ref "C105") (pin "2") (pinfunction "2_2") (pintype "passive"))
      (node (ref "C106") (pin "2") (pinfunction "2_2") (pintype "passive"))
      (node (ref "C107") (pin "2") (pinfunction "2_2") (pintype "passive"))
      (node (ref "C108") (pin "2") (pinfunction "2_2") (pintype "passive"))
      (node (ref "FR5") (pin "2") (pinfunction "2_2") (pintype "passive"))
      (node (ref "IC31") (pin "23") (pinfunction "Vdd_23") (pintype "passive"))
      (node (ref "IC31") (pin "8") (pinfunction "Vdd_8") (pintype "passive"))
      (node (ref "R147") (pin "2") (pinfunction "2_2") (pintype "passive"))
    )
    (net (code "65") (name "VCC3P3_LMK_VDDO") (class "Default")
      (node (ref "C112") (pin "2") (pinfunction "2_2") (pintype "passive"))
      (node (ref "C113") (pin "2") (pinfunction "2_2") (pintype "passive"))
      (node (ref "C114") (pin "2") (pinfunction "2_2") (pintype "passive"))
      (node (ref "C115") (pin "2") (pinfunction "2_2") (pintype "passive"))
      (node (ref "C116") (pin "2") (pinfunction "2_2") (pintype "passive"))
      (node (ref "C117") (pin "2") (pinfunction "2_2") (pintype "passive"))
      (node (ref "FR6") (pin "2") (pinfunction "2_2") (pintype "passive"))
      (node (ref "IC31") (pin "14") (pinfunction "Vddo_14") (pintype "passive"))
      (node (ref "IC31") (pin "18") (pinfunction "Vddo_18") (pintype "passive"))
      (node (ref "IC31") (pin "2") (pinfunction "Vddo_2") (pintype "passive"))
      (node (ref "IC31") (pin "6") (pinfunction "Vddo_6") (pintype "passive"))
    )
    (net (code "66") (name "unconnected-(IC31-OSCin-Pad9)") (class "Default")
      (node (ref "IC31") (pin "9") (pinfunction "OSCin_9") (pintype "passive+no_connect"))
    )
    (net (code "67") (name "unconnected-(IC31-OSCout-Pad10)") (class "Default")
      (node (ref "IC31") (pin "10") (pinfunction "OSCout_10") (pintype "passive+no_connect"))
    )
    (net (code "68") (name "unconnected-(IC32-NC-Pad4)") (class "Default")
      (node (ref "IC32") (pin "4") (pinfunction "NC_4") (pintype "passive+no_connect"))
    )
    (net (code "69") (name "unconnected-(XO2-T.S.-Pad3)") (class "Default")
      (node (ref "XO2") (pin "3") (pinfunction "T.S._3") (pintype "passive+no_connect"))
    )
    (net (code "70") (name "unconnected-(XO4-NC-Pad2)") (class "Default")
      (node (ref "XO4") (pin "2") (pinfunction "NC_2") (pintype "passive+no_connect"))
    )
    (net (code "71") (name "unconnected-(XO4-NC-Pad3)") (class "Default")
      (node (ref "XO4") (pin "3") (pinfunction "NC_3") (pintype "passive+no_connect"))
    )
    (net (code "72") (name "unconnected-(XO4-NC-Pad5)") (class "Default")
      (node (ref "XO4") (pin "5") (pinfunction "NC_5") (pintype "passive+no_connect"))
    )
    (net (code "73") (name "unconnected-(XO4-NC-Pad8)") (class "Default")
      (node (ref "XO4") (pin "8") (pinfunction "NC_8") (pintype "passive+no_connect"))
    )
    (net (code "74") (name "unconnected-(XO4-NC-Pad10)") (class "Default")
      (node (ref "XO4") (pin "10") (pinfunction "NC_10") (pintype "passive+no_connect"))
    )
  )
)
